# Power.net
KiCad netlist of a schematic drawn in Altium Designer
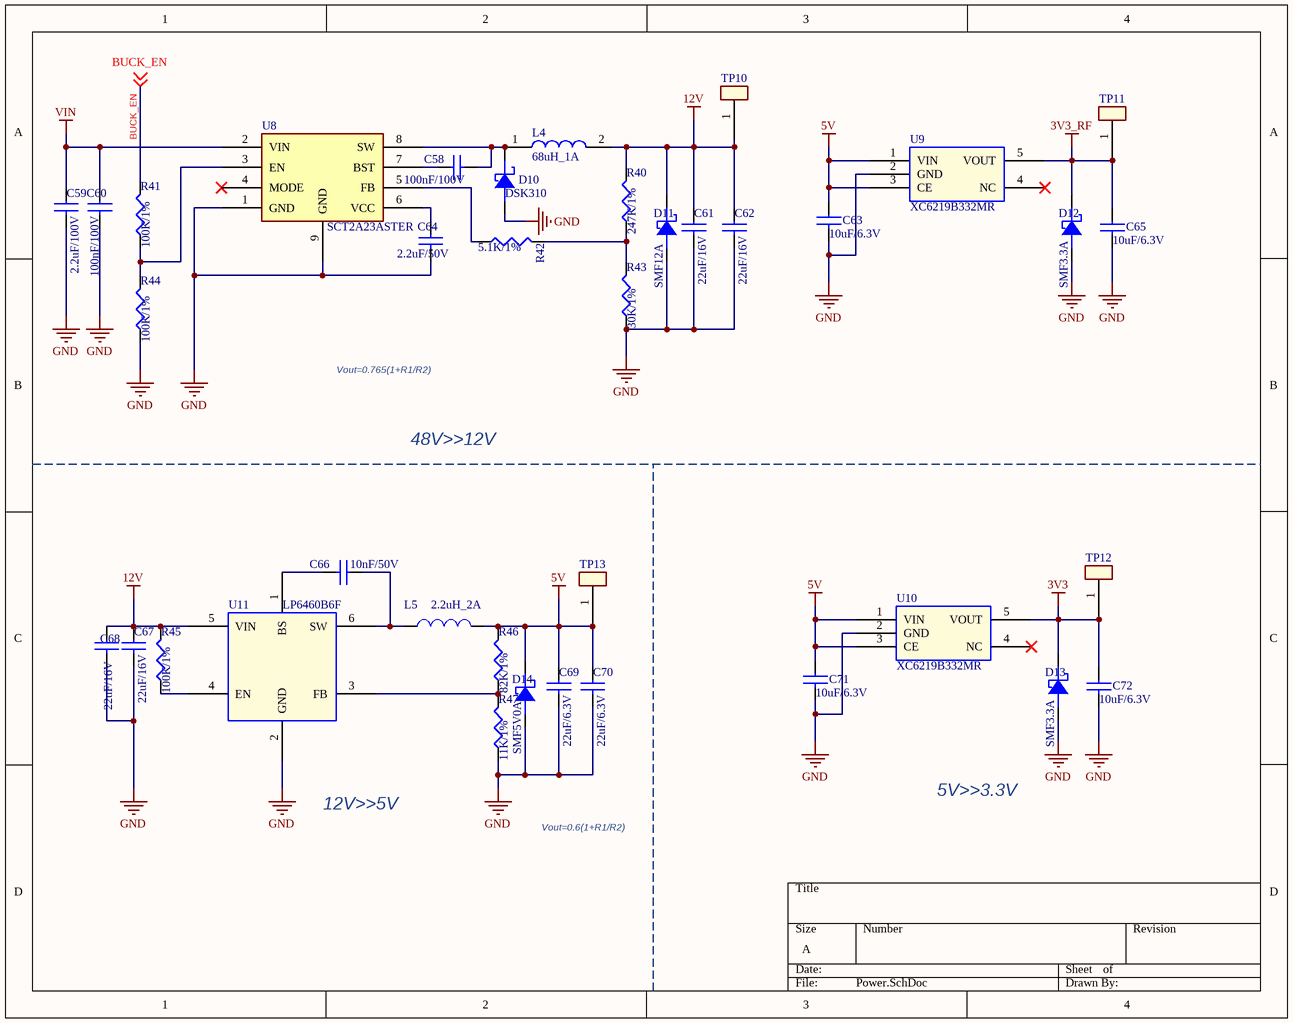
[diagram p0: Power.SchDoc]

(export (version "E")
  (design (tool "Eeschema 10.0.6"))
  (components
    (comp (ref "C58") (value "100nF/100V") (footprint "C0603") (libsource (lib "*") (part "CAP NP")))
    (comp (ref "C59") (value "2.2uF/100V") (footprint "C1206") (libsource (lib "*") (part "CAP NP")))
    (comp (ref "C60") (value "100nF/100V") (footprint "C0603") (libsource (lib "*") (part "CAP NP")))
    (comp (ref "C61") (value "22uF/16V") (footprint "C0805") (libsource (lib "*") (part "CAP NP")))
    (comp (ref "C62") (value "22uF/16V") (footprint "C0805") (libsource (lib "*") (part "CAP NP")))
    (comp (ref "C63") (value "10uF/6.3V") (footprint "C0402") (libsource (lib "*") (part "CAP NP")))
    (comp (ref "C64") (value "2.2uF/50V") (footprint "C0603") (libsource (lib "*") (part "CAP NP")))
    (comp (ref "C65") (value "10uF/6.3V") (footprint "C0402") (libsource (lib "*") (part "CAP NP")))
    (comp (ref "C66") (value "10nF/50V") (footprint "C0402") (libsource (lib "*") (part "CAP NP")))
    (comp (ref "C67") (value "22uF/16V") (footprint "C0805") (libsource (lib "*") (part "CAP NP")))
    (comp (ref "C68") (value "22uF/16V") (footprint "C0805") (libsource (lib "*") (part "CAP NP")))
    (comp (ref "C69") (value "22uF/6.3V") (footprint "C0805") (libsource (lib "*") (part "CAP NP")))
    (comp (ref "C70") (value "22uF/6.3V") (footprint "C0805") (libsource (lib "*") (part "CAP NP")))
    (comp (ref "C71") (value "10uF/6.3V") (footprint "C0402") (libsource (lib "*") (part "CAP NP")))
    (comp (ref "C72") (value "10uF/6.3V") (footprint "C0402") (libsource (lib "*") (part "CAP NP")))
    (comp (ref "D10") (value "DSK310") (footprint "SOD-123F") (libsource (lib "*") (part "DIODE SCHOTTKY21")))
    (comp (ref "D11") (value "SMF12A") (footprint "SOD-123F") (libsource (lib "*") (part "DIODE SCHOTTKY21")))
    (comp (ref "D12")
      (value "SMF3.3A")
      (footprint "SOD-123F")
      (libsource (lib "*") (part "DIODE SCHOTTKY21"))
    )
    (comp (ref "D13")
      (value "SMF3.3A")
      (footprint "SOD-123F")
      (libsource (lib "*") (part "DIODE SCHOTTKY21"))
    )
    (comp (ref "D14")
      (value "SMF5V0A")
      (footprint "SOD-123F")
      (libsource (lib "*") (part "DIODE SCHOTTKY21"))
    )
    (comp (ref "L4")
      (value "68uH_1A")
      (footprint "L5040")
      (description "Inductor")
      (fields
        (field (name "MANUFACTURER_PART_NUMBER") "74404054221")
        (field (name "MOUSER PART NUMBER") "710-74404054221")
      )
      (libsource (lib "VESC_DEVICE_Library") (part "74404054221"))
    )
    (comp (ref "L5") (value "2.2uH_2A") (footprint "L4020") (libsource (lib "*") (part "INDUCTOR")))
    (comp (ref "R40") (value "247K/1%") (footprint "R0402") (libsource (lib "*") (part "RESISTOR")))
    (comp (ref "R41") (value "100K/1%") (footprint "R0402") (libsource (lib "*") (part "RESISTOR")))
    (comp (ref "R42") (value "5.1K/1%") (footprint "R0402") (libsource (lib "*") (part "RESISTOR")))
    (comp (ref "R43") (value "30K/1%") (footprint "R0402") (libsource (lib "*") (part "RESISTOR")))
    (comp (ref "R44") (value "100K/1%") (footprint "R0402") (libsource (lib "*") (part "RESISTOR")))
    (comp (ref "R45") (value "100K/1%") (footprint "R0402") (libsource (lib "*") (part "RESISTOR")))
    (comp (ref "R46") (value "82K/1%") (footprint "R0402") (libsource (lib "*") (part "RESISTOR")))
    (comp (ref "R47") (value "11K/1%") (footprint "R0402") (libsource (lib "*") (part "RESISTOR")))
    (comp (ref "TP10")
      (value "TEST POINT")
      (footprint "test_point_100_smd")
      (libsource (lib "VESC_DEVICE_Library") (part "TEST POINT"))
    )
    (comp (ref "TP11")
      (value "TEST POINT")
      (footprint "test_point_100_smd")
      (libsource (lib "VESC_DEVICE_Library") (part "TEST POINT"))
    )
    (comp (ref "TP12")
      (value "TEST POINT")
      (footprint "test_point_100_smd")
      (libsource (lib "VESC_DEVICE_Library") (part "TEST POINT"))
    )
    (comp (ref "TP13")
      (value "TEST POINT")
      (footprint "test_point_100_smd")
      (libsource (lib "VESC_DEVICE_Library") (part "TEST POINT"))
    )
    (comp (ref "U8")
      (value "SCT2A23ASTER")
      (footprint "ESOP-8_L4.9-W3.9-P1.27-LS6.0-BL-EP")
      (fields (field (name "MANUFACTURER") "SCT(芯洲科技)"))
      (libsource (lib "VESC_DEVICE_Library") (part "SCT2A23ASTER"))
    )
    (comp (ref "U9")
      (value "XC6219B332MR")
      (footprint "SOT-23-5")
      (libsource (lib "*") (part "XC6219B332MR"))
    )
    (comp (ref "U10")
      (value "XC6219B332MR")
      (footprint "SOT-23-5")
      (libsource (lib "*") (part "XC6219B332MR"))
    )
    (comp (ref "U11") (value "LP6460B6F") (footprint "SOT-23-6") (libsource (lib "*") (part "LP6460B6F")))
  )
  (nets
    (net (code "1") (name "3V3") (class "Default")
      (node (ref "C72") (pin "1") (pinfunction "1_1") (pintype "passive"))
      (node (ref "D13") (pin "1") (pinfunction "K_1") (pintype "passive"))
      (node (ref "TP12") (pin "1") (pinfunction "1_1") (pintype "passive"))
      (node (ref "U10") (pin "5") (pinfunction "VOUT_5") (pintype "passive"))
    )
    (net (code "2") (name "3V3_RF") (class "Default")
      (node (ref "C65") (pin "1") (pinfunction "1_1") (pintype "passive"))
      (node (ref "D12") (pin "1") (pinfunction "K_1") (pintype "passive"))
      (node (ref "TP11") (pin "1") (pinfunction "1_1") (pintype "passive"))
      (node (ref "U9") (pin "5") (pinfunction "VOUT_5") (pintype "passive"))
    )
    (net (code "3") (name "5V") (class "Default")
      (node (ref "C63") (pin "1") (pinfunction "1_1") (pintype "passive"))
      (node (ref "C69") (pin "1") (pinfunction "1_1") (pintype "passive"))
      (node (ref "C70") (pin "1") (pinfunction "1_1") (pintype "passive"))
      (node (ref "C71") (pin "1") (pinfunction "1_1") (pintype "passive"))
      (node (ref "D14") (pin "1") (pinfunction "K_1") (pintype "passive"))
      (node (ref "L5") (pin "2") (pinfunction "2_2") (pintype "passive"))
      (node (ref "R46") (pin "2") (pinfunction "2_2") (pintype "passive"))
      (node (ref "TP13") (pin "1") (pinfunction "1_1") (pintype "passive"))
      (node (ref "U10") (pin "1") (pinfunction "VIN_1") (pintype "passive"))
      (node (ref "U10") (pin "3") (pinfunction "CE_3") (pintype "passive"))
      (node (ref "U9") (pin "1") (pinfunction "VIN_1") (pintype "passive"))
      (node (ref "U9") (pin "3") (pinfunction "CE_3") (pintype "passive"))
    )
    (net (code "4") (name "12V") (class "Default")
      (node (ref "C61") (pin "1") (pinfunction "1_1") (pintype "passive"))
      (node (ref "C62") (pin "1") (pinfunction "1_1") (pintype "passive"))
      (node (ref "C67") (pin "1") (pinfunction "1_1") (pintype "passive"))
      (node (ref "C68") (pin "1") (pinfunction "1_1") (pintype "passive"))
      (node (ref "D11") (pin "1") (pinfunction "K_1") (pintype "passive"))
      (node (ref "L4") (pin "2") (pinfunction "2_2") (pintype "passive"))
      (node (ref "R40") (pin "2") (pinfunction "2_2") (pintype "passive"))
      (node (ref "R45") (pin "2") (pinfunction "2_2") (pintype "passive"))
      (node (ref "TP10") (pin "1") (pinfunction "1_1") (pintype "passive"))
      (node (ref "U11") (pin "5") (pinfunction "VIN_5") (pintype "passive"))
    )
    (net (code "5") (name "BUCK_EN") (class "Default")
      (node (ref "R41") (pin "2") (pinfunction "2_2") (pintype "passive"))
    )
    (net (code "6") (name "GND") (class "Default")
      (node (ref "C59") (pin "2") (pinfunction "2_2") (pintype "passive"))
      (node (ref "C60") (pin "2") (pinfunction "2_2") (pintype "passive"))
      (node (ref "C61") (pin "2") (pinfunction "2_2") (pintype "passive"))
      (node (ref "C62") (pin "2") (pinfunction "2_2") (pintype "passive"))
      (node (ref "C63") (pin "2") (pinfunction "2_2") (pintype "passive"))
      (node (ref "C64") (pin "2") (pinfunction "2_2") (pintype "passive"))
      (node (ref "C65") (pin "2") (pinfunction "2_2") (pintype "passive"))
      (node (ref "C67") (pin "2") (pinfunction "2_2") (pintype "passive"))
      (node (ref "C68") (pin "2") (pinfunction "2_2") (pintype "passive"))
      (node (ref "C69") (pin "2") (pinfunction "2_2") (pintype "passive"))
      (node (ref "C70") (pin "2") (pinfunction "2_2") (pintype "passive"))
      (node (ref "C71") (pin "2") (pinfunction "2_2") (pintype "passive"))
      (node (ref "C72") (pin "2") (pinfunction "2_2") (pintype "passive"))
      (node (ref "D10") (pin "2") (pinfunction "A_2") (pintype "passive"))
      (node (ref "D11") (pin "2") (pinfunction "A_2") (pintype "passive"))
      (node (ref "D12") (pin "2") (pinfunction "A_2") (pintype "passive"))
      (node (ref "D13") (pin "2") (pinfunction "A_2") (pintype "passive"))
      (node (ref "D14") (pin "2") (pinfunction "A_2") (pintype "passive"))
      (node (ref "R43") (pin "1") (pinfunction "1_1") (pintype "passive"))
      (node (ref "R44") (pin "1") (pinfunction "1_1") (pintype "passive"))
      (node (ref "R47") (pin "1") (pinfunction "1_1") (pintype "passive"))
      (node (ref "U10") (pin "2") (pinfunction "GND_2") (pintype "passive"))
      (node (ref "U11") (pin "2") (pinfunction "GND_2") (pintype "passive"))
      (node (ref "U8") (pin "1") (pinfunction "GND_1") (pintype "power_in"))
      (node (ref "U8") (pin "9") (pinfunction "GND_9") (pintype "power_in"))
      (node (ref "U9") (pin "2") (pinfunction "GND_2") (pintype "passive"))
    )
    (net (code "7") (name "Net-(D10-K)") (class "Default")
      (node (ref "C58") (pin "2") (pinfunction "2_2") (pintype "passive"))
      (node (ref "D10") (pin "1") (pinfunction "K_1") (pintype "passive"))
      (node (ref "L4") (pin "1") (pinfunction "1_1") (pintype "passive"))
      (node (ref "U8") (pin "8") (pinfunction "SW_8") (pintype "passive"))
    )
    (net (code "8") (name "Net-(R40-Pad1)") (class "Default")
      (node (ref "R40") (pin "1") (pinfunction "1_1") (pintype "passive"))
      (node (ref "R42") (pin "2") (pinfunction "2_2") (pintype "passive"))
      (node (ref "R43") (pin "2") (pinfunction "2_2") (pintype "passive"))
    )
    (net (code "9") (name "Net-(U8-BST)") (class "Default")
      (node (ref "C58") (pin "1") (pinfunction "1_1") (pintype "passive"))
      (node (ref "U8") (pin "7") (pinfunction "BST_7") (pintype "passive"))
    )
    (net (code "10") (name "Net-(U8-EN)") (class "Default")
      (node (ref "R41") (pin "1") (pinfunction "1_1") (pintype "passive"))
      (node (ref "R44") (pin "2") (pinfunction "2_2") (pintype "passive"))
      (node (ref "U8") (pin "3") (pinfunction "EN_3") (pintype "passive"))
    )
    (net (code "11") (name "Net-(U8-FB)") (class "Default")
      (node (ref "R42") (pin "1") (pinfunction "1_1") (pintype "passive"))
      (node (ref "U8") (pin "5") (pinfunction "FB_5") (pintype "passive"))
    )
    (net (code "12") (name "Net-(U8-VCC)") (class "Default")
      (node (ref "C64") (pin "1") (pinfunction "1_1") (pintype "passive"))
      (node (ref "U8") (pin "6") (pinfunction "VCC_6") (pintype "passive"))
    )
    (net (code "13") (name "Net-(U11-BS)") (class "Default")
      (node (ref "C66") (pin "2") (pinfunction "2_2") (pintype "passive"))
      (node (ref "U11") (pin "1") (pinfunction "BS_1") (pintype "passive"))
    )
    (net (code "14") (name "Net-(U11-EN)") (class "Default")
      (node (ref "R45") (pin "1") (pinfunction "1_1") (pintype "passive"))
      (node (ref "U11") (pin "4") (pinfunction "EN_4") (pintype "passive"))
    )
    (net (code "15") (name "Net-(U11-FB)") (class "Default")
      (node (ref "R46") (pin "1") (pinfunction "1_1") (pintype "passive"))
      (node (ref "R47") (pin "2") (pinfunction "2_2") (pintype "passive"))
      (node (ref "U11") (pin "3") (pinfunction "FB_3") (pintype "passive"))
    )
    (net (code "16") (name "Net-(U11-SW)") (class "Default")
      (node (ref "C66") (pin "1") (pinfunction "1_1") (pintype "passive"))
      (node (ref "L5") (pin "1") (pinfunction "1_1") (pintype "passive"))
      (node (ref "U11") (pin "6") (pinfunction "SW_6") (pintype "passive"))
    )
    (net (code "17") (name "VIN") (class "Default")
      (node (ref "C59") (pin "1") (pinfunction "1_1") (pintype "passive"))
      (node (ref "C60") (pin "1") (pinfunction "1_1") (pintype "passive"))
      (node (ref "U8") (pin "2") (pinfunction "VIN_2") (pintype "power_in"))
    )
    (net (code "18") (name "unconnected-(U8-MODE-Pad4)") (class "Default")
      (node (ref "U8") (pin "4") (pinfunction "MODE_4") (pintype "passive+no_connect"))
    )
    (net (code "19") (name "unconnected-(U9-NC-Pad4)") (class "Default")
      (node (ref "U9") (pin "4") (pinfunction "NC_4") (pintype "passive+no_connect"))
    )
    (net (code "20") (name "unconnected-(U10-NC-Pad4)") (class "Default")
      (node (ref "U10") (pin "4") (pinfunction "NC_4") (pintype "passive+no_connect"))
    )
  )
)
